# adapter-board-stepper.net
KiCad netlist of a schematic drawn in EAGLE
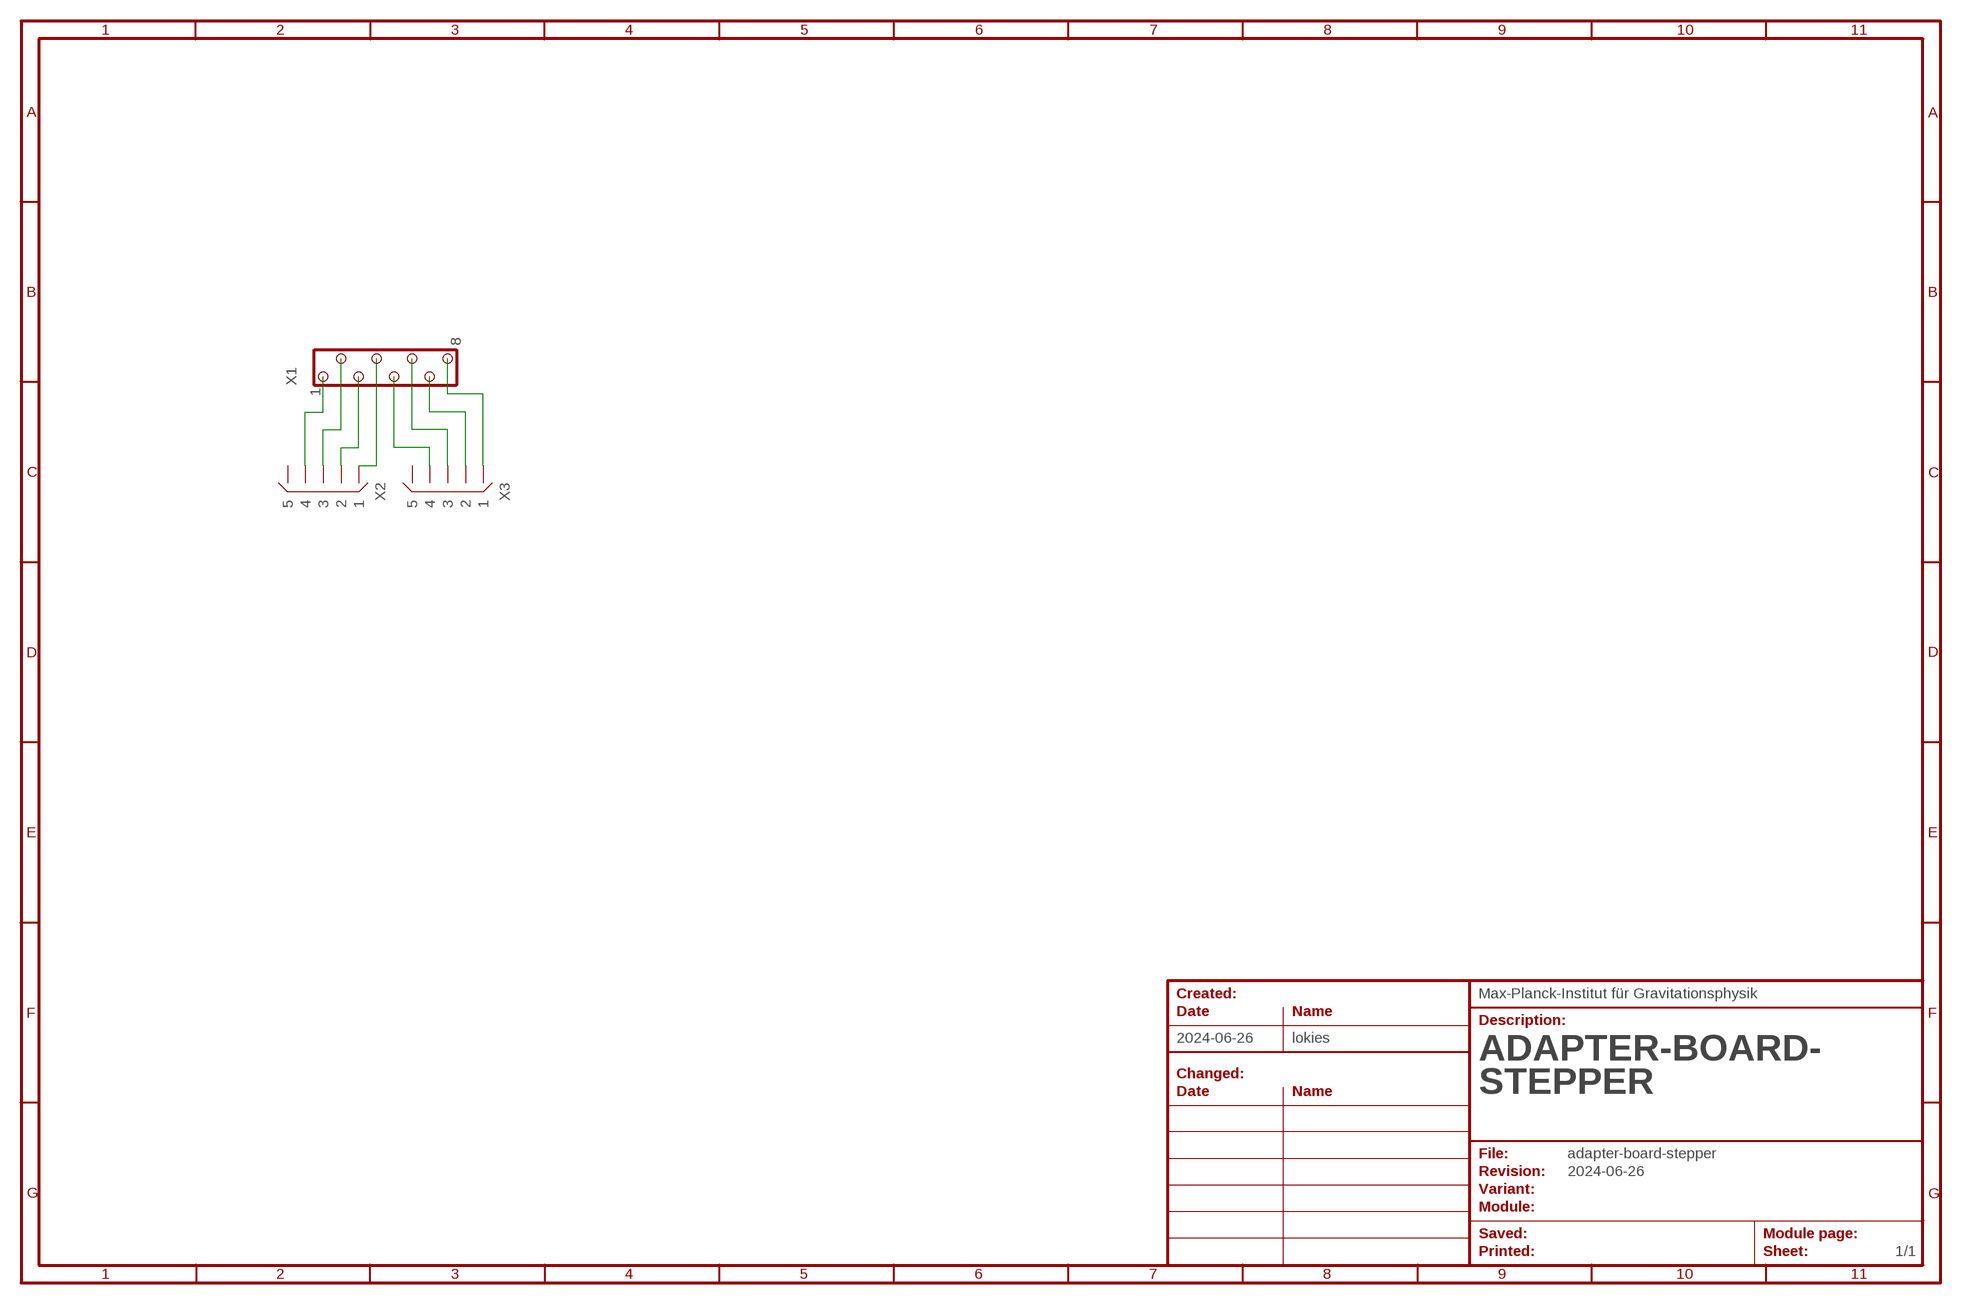
[diagram p0: schematic, sheet 1]

(export (version "E")
  (design (tool "Eeschema 10.0.6"))
  (components
    (comp (ref "X1")
      (value "XS08-RJ45")
      (footprint "eagle-import:XS08-2S-RJ45")
      (libsource (lib "eagle-import") (part "XS08-RJ45"))
    )
    (comp (ref "X2")
      (value "X05-SIL-MALE-VERT-L")
      (footprint "eagle-import:X05-SIL-MALE-VERT-L")
      (libsource (lib "eagle-import") (part "X05-SIL-MALE-VERT-L"))
    )
    (comp (ref "X3")
      (value "X05-SIL-MALE-VERT-L")
      (footprint "eagle-import:X05-SIL-MALE-VERT-L")
      (libsource (lib "eagle-import") (part "X05-SIL-MALE-VERT-L"))
    )
  )
  (nets
    (net (code "1") (name "Net-(X1-Pad1)") (class "Default")
      (node (ref "X1") (pin "1") (pinfunction "1_1") (pintype "bidirectional"))
      (node (ref "X2") (pin "4") (pinfunction "4_4") (pintype "bidirectional"))
    )
    (net (code "2") (name "Net-(X1-Pad2)") (class "Default")
      (node (ref "X1") (pin "2") (pinfunction "2_2") (pintype "bidirectional"))
      (node (ref "X2") (pin "3") (pinfunction "3_3") (pintype "bidirectional"))
    )
    (net (code "3") (name "Net-(X1-Pad3)") (class "Default")
      (node (ref "X1") (pin "3") (pinfunction "3_3") (pintype "bidirectional"))
      (node (ref "X2") (pin "2") (pinfunction "2_2") (pintype "bidirectional"))
    )
    (net (code "4") (name "Net-(X1-Pad4)") (class "Default")
      (node (ref "X1") (pin "4") (pinfunction "4_4") (pintype "bidirectional"))
      (node (ref "X2") (pin "1") (pinfunction "1_1") (pintype "bidirectional"))
    )
    (net (code "5") (name "Net-(X1-Pad5)") (class "Default")
      (node (ref "X1") (pin "5") (pinfunction "5_5") (pintype "bidirectional"))
      (node (ref "X3") (pin "4") (pinfunction "4_4") (pintype "bidirectional"))
    )
    (net (code "6") (name "Net-(X1-Pad6)") (class "Default")
      (node (ref "X1") (pin "6") (pinfunction "6_6") (pintype "bidirectional"))
      (node (ref "X3") (pin "3") (pinfunction "3_3") (pintype "bidirectional"))
    )
    (net (code "7") (name "Net-(X1-Pad7)") (class "Default")
      (node (ref "X1") (pin "7") (pinfunction "7_7") (pintype "bidirectional"))
      (node (ref "X3") (pin "2") (pinfunction "2_2") (pintype "bidirectional"))
    )
    (net (code "8") (name "Net-(X1-Pad8)") (class "Default")
      (node (ref "X1") (pin "8") (pinfunction "8_8") (pintype "bidirectional"))
      (node (ref "X3") (pin "1") (pinfunction "1_1") (pintype "bidirectional"))
    )
    (net (code "9") (name "unconnected-(X2-Pad5)") (class "Default")
      (node (ref "X2") (pin "5") (pinfunction "5_5") (pintype "bidirectional"))
    )
    (net (code "10") (name "unconnected-(X3-Pad5)") (class "Default")
      (node (ref "X3") (pin "5") (pinfunction "5_5") (pintype "bidirectional"))
    )
  )
)
